# USB.net
KiCad netlist of a schematic drawn in EasyEDA Pro
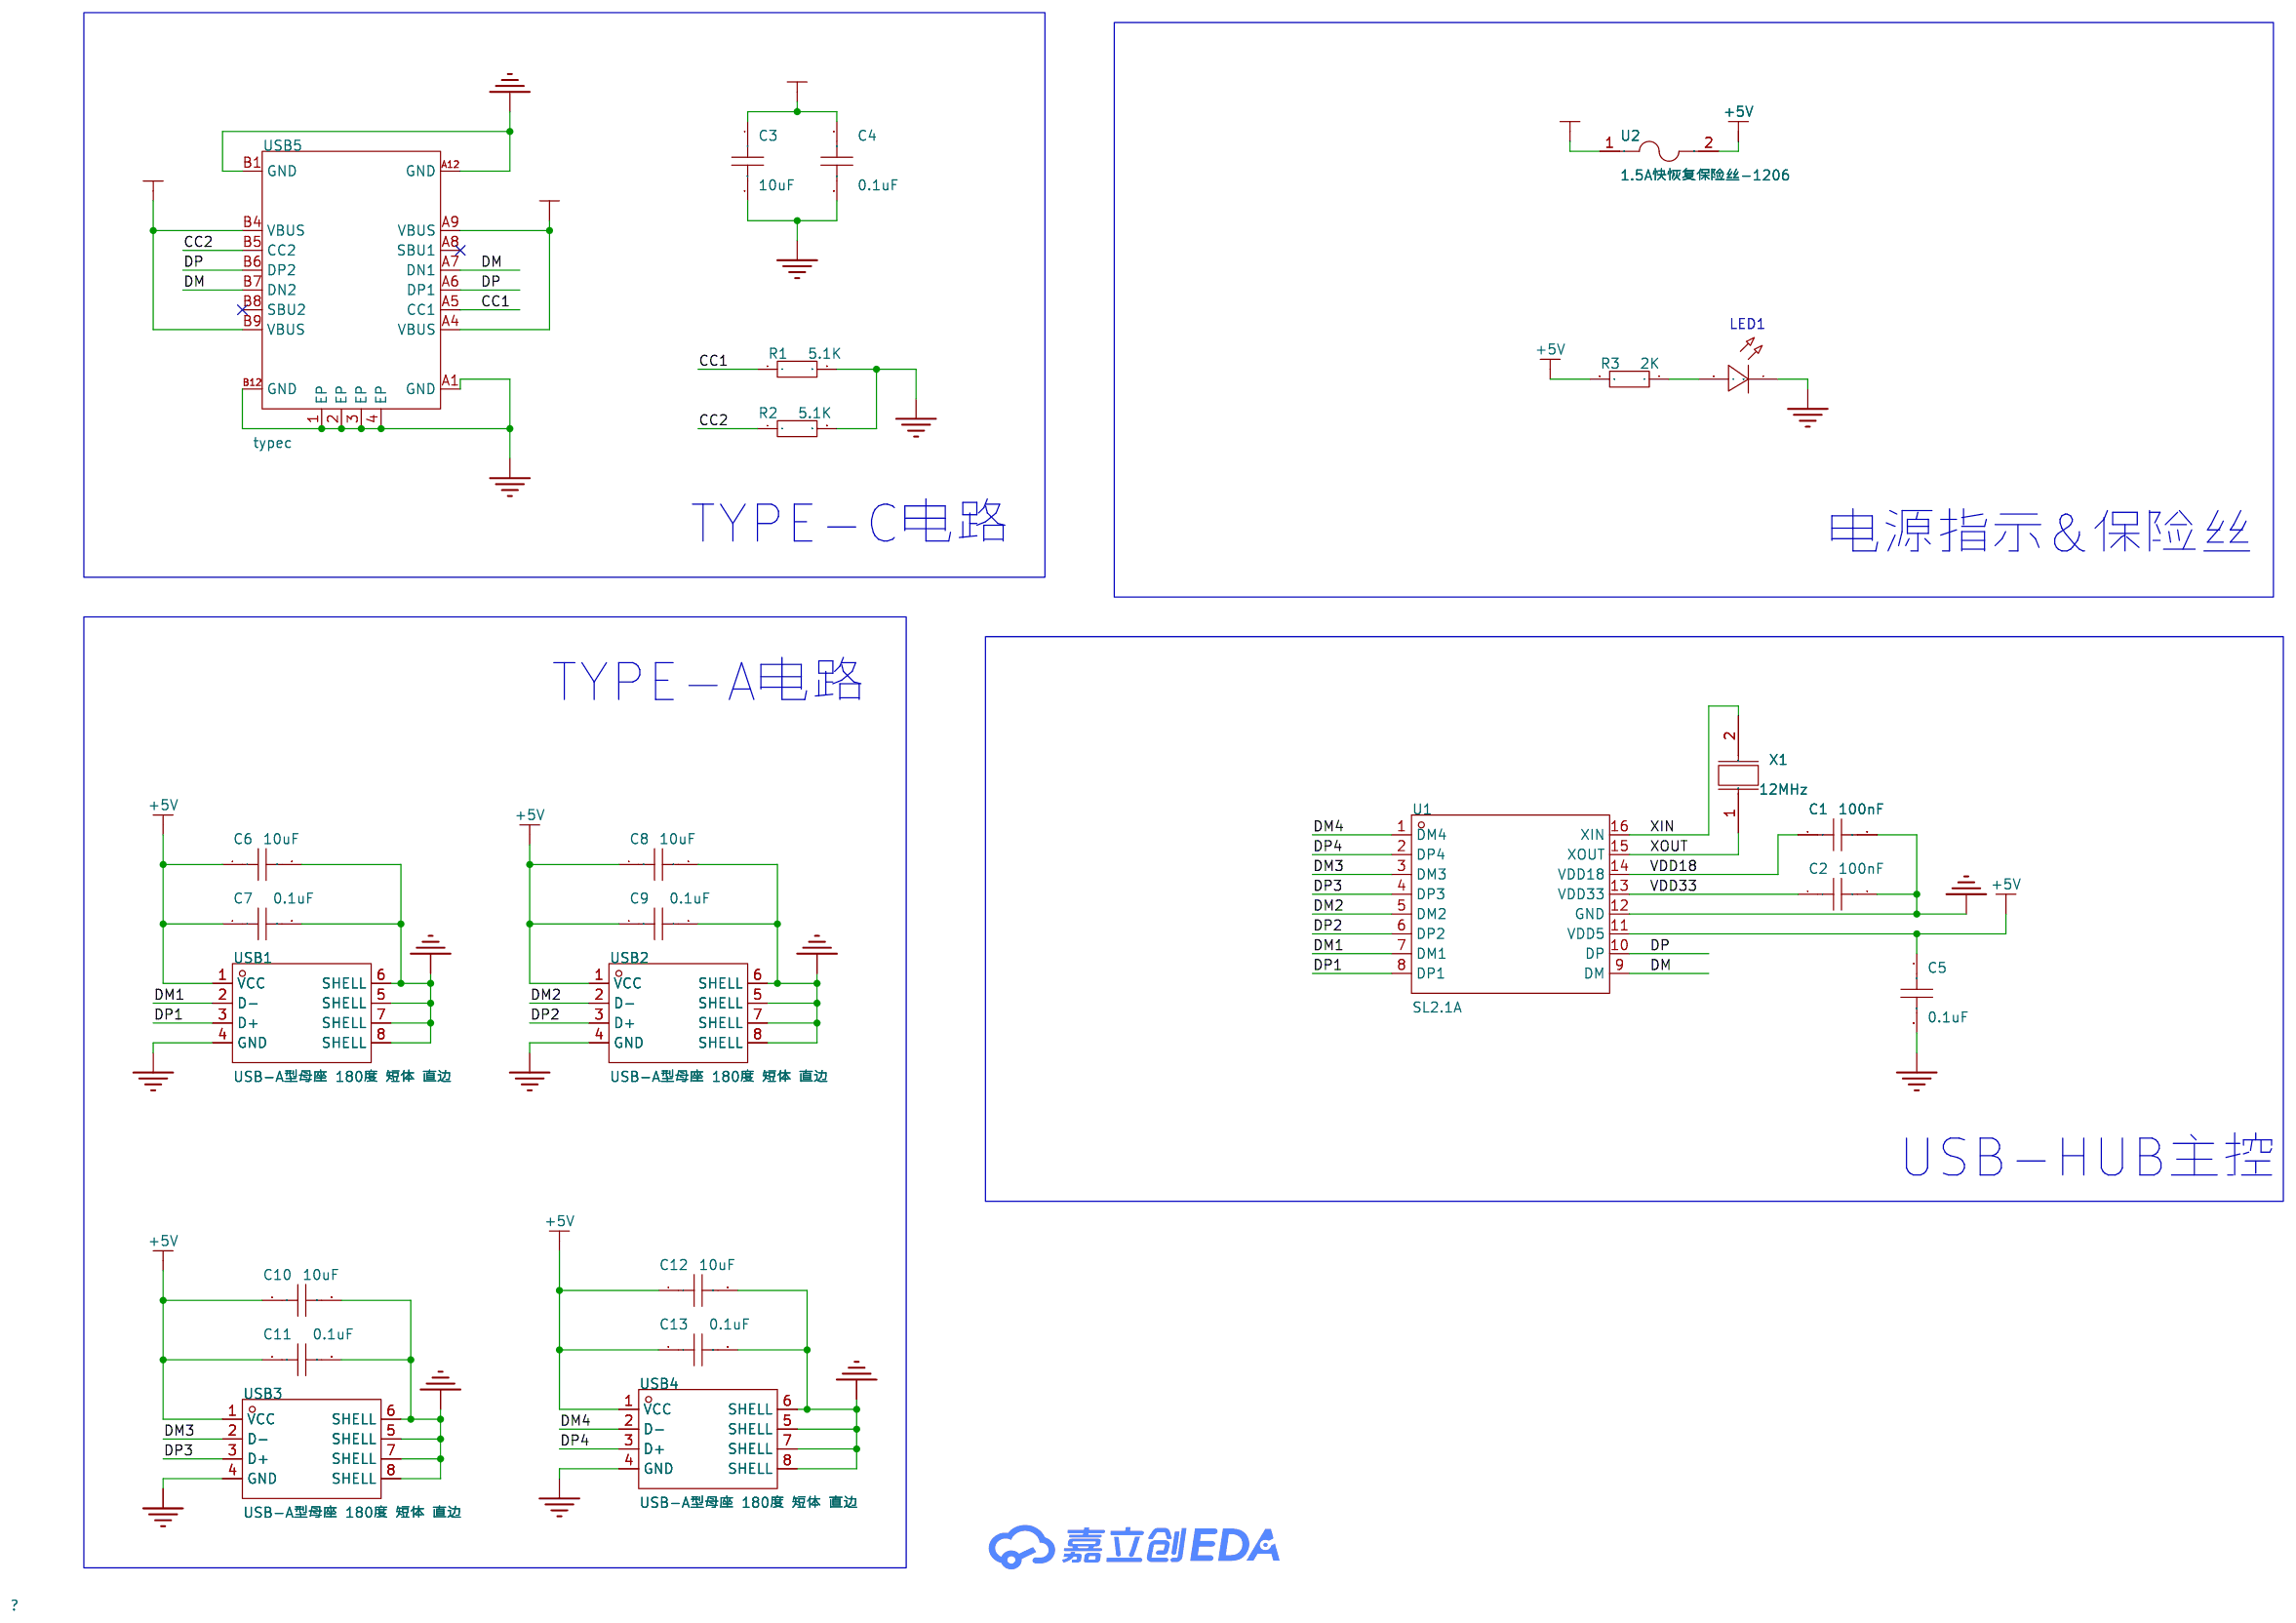
[diagram p0: schematic sheet]

(export (version "E")
  (design (tool "Eeschema 10.0.6"))
  (components
    (comp (ref "C1")
      (value "100nF")
      (footprint "easyedapro:C0805")
      (libsource (lib "easyedapro") (part "CapAcitance"))
    )
    (comp (ref "C2")
      (value "100nF")
      (footprint "easyedapro:C0805")
      (libsource (lib "easyedapro") (part "CapAcitance"))
    )
    (comp (ref "C3")
      (value "10uF")
      (footprint "easyedapro:C0805")
      (libsource (lib "easyedapro") (part "CapAcitance"))
    )
    (comp (ref "C4")
      (value "0.1uF")
      (footprint "easyedapro:C0805")
      (libsource (lib "easyedapro") (part "CapAcitance"))
    )
    (comp (ref "C5")
      (value "0.1uF")
      (footprint "easyedapro:C0805")
      (libsource (lib "easyedapro") (part "CapAcitance"))
    )
    (comp (ref "C6")
      (value "10uF")
      (footprint "easyedapro:C0805")
      (libsource (lib "easyedapro") (part "CapAcitance"))
    )
    (comp (ref "C7")
      (value "0.1uF")
      (footprint "easyedapro:C0805")
      (libsource (lib "easyedapro") (part "CapAcitance"))
    )
    (comp (ref "C8")
      (value "10uF")
      (footprint "easyedapro:C0805")
      (libsource (lib "easyedapro") (part "CapAcitance"))
    )
    (comp (ref "C9")
      (value "0.1uF")
      (footprint "easyedapro:C0805")
      (libsource (lib "easyedapro") (part "CapAcitance"))
    )
    (comp (ref "C10")
      (value "10uF")
      (footprint "easyedapro:C0805")
      (libsource (lib "easyedapro") (part "CapAcitance"))
    )
    (comp (ref "C11")
      (value "0.1uF")
      (footprint "easyedapro:C0805")
      (libsource (lib "easyedapro") (part "CapAcitance"))
    )
    (comp (ref "C12")
      (value "10uF")
      (footprint "easyedapro:C0805")
      (libsource (lib "easyedapro") (part "CapAcitance"))
    )
    (comp (ref "C13")
      (value "0.1uF")
      (footprint "easyedapro:C0805")
      (libsource (lib "easyedapro") (part "CapAcitance"))
    )
    (comp (ref "LED1")
      (value "~")
      (footprint "easyedapro:LED_0805")
      (libsource (lib "easyedapro") (part "LED_G"))
    )
    (comp (ref "R1") (value "5.1K") (footprint "easyedapro:R0603") (libsource (lib "easyedapro") (part "电阻")))
    (comp (ref "R2") (value "5.1K") (footprint "easyedapro:R0603") (libsource (lib "easyedapro") (part "电阻")))
    (comp (ref "R3") (value "2K") (footprint "easyedapro:R0603") (libsource (lib "easyedapro") (part "电阻")))
    (comp (ref "U1")
      (value "SL2.1A")
      (footprint "easyedapro:SOP-16_L10.0-W3.9-P1.27-LS6.0-BL")
      (description "SL2.1A是一颗高集成度,高性能,低功耗的USB2.0集线器主控芯片，支持USB2.0高速(480MHz),全速(12MHz)和低速模式(1.5MHz)，内置12MHz晶体振荡器。")
      (fields (field (name "Manufacturer") "CoreChips(和芯润德)"))
      (libsource (lib "easyedapro") (part "SL2.1A"))
    )
    (comp (ref "U2")
      (value "1.5A快恢复保险丝-1206")
      (footprint "easyedapro:F1206")
      (libsource (lib "easyedapro") (part "1.5A快恢复保险丝-1206"))
    )
    (comp (ref "USB1")
      (value "USB-A型母座 180度 短体 直边")
      (footprint "easyedapro:USB-A-SMD_WT_C9900004571")
      (libsource (lib "easyedapro") (part "USB-A型母座 180度 短体 直边"))
    )
    (comp (ref "USB2")
      (value "USB-A型母座 180度 短体 直边")
      (footprint "easyedapro:USB-A-SMD_WT_C9900004571")
      (libsource (lib "easyedapro") (part "USB-A型母座 180度 短体 直边"))
    )
    (comp (ref "USB3")
      (value "USB-A型母座 180度 短体 直边")
      (footprint "easyedapro:USB-A-SMD_WT_C9900004571")
      (libsource (lib "easyedapro") (part "USB-A型母座 180度 短体 直边"))
    )
    (comp (ref "USB4")
      (value "USB-A型母座 180度 短体 直边")
      (footprint "easyedapro:USB-A-SMD_WT_C9900004571")
      (libsource (lib "easyedapro") (part "USB-A型母座 180度 短体 直边"))
    )
    (comp (ref "USB5")
      (value "typec")
      (footprint "easyedapro:USB-C-SMD_KH-TYPE-C-16P")
      (libsource (lib "easyedapro") (part "TYPEC_C9900016956"))
    )
    (comp (ref "X1")
      (value "12MHz")
      (footprint "easyedapro:CRYSTAL-SMD_L5.0-W3.2-1-A")
      (libsource (lib "easyedapro") (part "12MHZ"))
    )
  )
  (nets
    (net (code "1") (name "+5V") (class "Default")
      (node (ref "C10") (pin "1") (pinfunction "1_1") (pintype "input"))
      (node (ref "C11") (pin "1") (pinfunction "1_1") (pintype "input"))
      (node (ref "C12") (pin "1") (pinfunction "1_1") (pintype "input"))
      (node (ref "C13") (pin "1") (pinfunction "1_1") (pintype "input"))
      (node (ref "C5") (pin "1") (pinfunction "1_1") (pintype "input"))
      (node (ref "C6") (pin "1") (pinfunction "1_1") (pintype "input"))
      (node (ref "C7") (pin "1") (pinfunction "1_1") (pintype "input"))
      (node (ref "C8") (pin "1") (pinfunction "1_1") (pintype "input"))
      (node (ref "C9") (pin "1") (pinfunction "1_1") (pintype "input"))
      (node (ref "R3") (pin "2") (pinfunction "2_2") (pintype "input"))
      (node (ref "U1") (pin "11") (pinfunction "VDD5_11") (pintype "unspecified"))
      (node (ref "U2") (pin "2") (pinfunction "2_2") (pintype "unspecified"))
      (node (ref "USB1") (pin "1") (pinfunction "VCC_1") (pintype "unspecified"))
      (node (ref "USB2") (pin "1") (pinfunction "VCC_1") (pintype "unspecified"))
      (node (ref "USB3") (pin "1") (pinfunction "VCC_1") (pintype "unspecified"))
      (node (ref "USB4") (pin "1") (pinfunction "VCC_1") (pintype "unspecified"))
    )
    (net (code "2") (name "/CC1") (class "Default")
      (node (ref "R1") (pin "1") (pinfunction "1_1") (pintype "input"))
      (node (ref "USB5") (pin "A5") (pinfunction "CC1_A5") (pintype "unspecified"))
    )
    (net (code "3") (name "/CC2") (class "Default")
      (node (ref "R2") (pin "1") (pinfunction "1_1") (pintype "input"))
      (node (ref "USB5") (pin "B5") (pinfunction "CC2_B5") (pintype "unspecified"))
    )
    (net (code "4") (name "/DM") (class "Default")
      (node (ref "U1") (pin "9") (pinfunction "DM_9") (pintype "unspecified"))
      (node (ref "USB5") (pin "A7") (pinfunction "DN1_A7") (pintype "unspecified"))
      (node (ref "USB5") (pin "B7") (pinfunction "DN2_B7") (pintype "unspecified"))
    )
    (net (code "5") (name "/DM1") (class "Default")
      (node (ref "U1") (pin "7") (pinfunction "DM1_7") (pintype "unspecified"))
      (node (ref "USB1") (pin "2") (pinfunction "D-_2") (pintype "unspecified"))
    )
    (net (code "6") (name "/DM2") (class "Default")
      (node (ref "U1") (pin "5") (pinfunction "DM2_5") (pintype "unspecified"))
      (node (ref "USB2") (pin "2") (pinfunction "D-_2") (pintype "unspecified"))
    )
    (net (code "7") (name "/DM3") (class "Default")
      (node (ref "U1") (pin "3") (pinfunction "DM3_3") (pintype "unspecified"))
      (node (ref "USB3") (pin "2") (pinfunction "D-_2") (pintype "unspecified"))
    )
    (net (code "8") (name "/DM4") (class "Default")
      (node (ref "U1") (pin "1") (pinfunction "DM4_1") (pintype "unspecified"))
      (node (ref "USB4") (pin "2") (pinfunction "D-_2") (pintype "unspecified"))
    )
    (net (code "9") (name "/DP") (class "Default")
      (node (ref "U1") (pin "10") (pinfunction "DP_10") (pintype "unspecified"))
      (node (ref "USB5") (pin "A6") (pinfunction "DP1_A6") (pintype "unspecified"))
      (node (ref "USB5") (pin "B6") (pinfunction "DP2_B6") (pintype "unspecified"))
    )
    (net (code "10") (name "/DP1") (class "Default")
      (node (ref "U1") (pin "8") (pinfunction "DP1_8") (pintype "unspecified"))
      (node (ref "USB1") (pin "3") (pinfunction "D+_3") (pintype "unspecified"))
    )
    (net (code "11") (name "/DP2") (class "Default")
      (node (ref "U1") (pin "6") (pinfunction "DP2_6") (pintype "unspecified"))
      (node (ref "USB2") (pin "3") (pinfunction "D+_3") (pintype "unspecified"))
    )
    (net (code "12") (name "/DP3") (class "Default")
      (node (ref "U1") (pin "4") (pinfunction "DP3_4") (pintype "unspecified"))
      (node (ref "USB3") (pin "3") (pinfunction "D+_3") (pintype "unspecified"))
    )
    (net (code "13") (name "/DP4") (class "Default")
      (node (ref "U1") (pin "2") (pinfunction "DP4_2") (pintype "unspecified"))
      (node (ref "USB4") (pin "3") (pinfunction "D+_3") (pintype "unspecified"))
    )
    (net (code "14") (name "/VDD18") (class "Default")
      (node (ref "C1") (pin "1") (pinfunction "1_1") (pintype "input"))
      (node (ref "U1") (pin "14") (pinfunction "VDD18_14") (pintype "unspecified"))
    )
    (net (code "15") (name "/VDD33") (class "Default")
      (node (ref "C2") (pin "1") (pinfunction "1_1") (pintype "input"))
      (node (ref "U1") (pin "13") (pinfunction "VDD33_13") (pintype "unspecified"))
    )
    (net (code "16") (name "/XIN") (class "Default")
      (node (ref "U1") (pin "16") (pinfunction "XIN_16") (pintype "unspecified"))
      (node (ref "X1") (pin "2") (pinfunction "2_2") (pintype "unspecified"))
    )
    (net (code "17") (name "/XOUT") (class "Default")
      (node (ref "U1") (pin "15") (pinfunction "XOUT_15") (pintype "unspecified"))
      (node (ref "X1") (pin "1") (pinfunction "1_1") (pintype "unspecified"))
    )
    (net (code "18") (name "GND") (class "Default")
      (node (ref "C1") (pin "2") (pinfunction "2_2") (pintype "input"))
      (node (ref "C10") (pin "2") (pinfunction "2_2") (pintype "input"))
      (node (ref "C11") (pin "2") (pinfunction "2_2") (pintype "input"))
      (node (ref "C12") (pin "2") (pinfunction "2_2") (pintype "input"))
      (node (ref "C13") (pin "2") (pinfunction "2_2") (pintype "input"))
      (node (ref "C2") (pin "2") (pinfunction "2_2") (pintype "input"))
      (node (ref "C3") (pin "2") (pinfunction "2_2") (pintype "input"))
      (node (ref "C4") (pin "2") (pinfunction "2_2") (pintype "input"))
      (node (ref "C5") (pin "2") (pinfunction "2_2") (pintype "input"))
      (node (ref "C6") (pin "2") (pinfunction "2_2") (pintype "input"))
      (node (ref "C7") (pin "2") (pinfunction "2_2") (pintype "input"))
      (node (ref "C8") (pin "2") (pinfunction "2_2") (pintype "input"))
      (node (ref "C9") (pin "2") (pinfunction "2_2") (pintype "input"))
      (node (ref "LED1") (pin "1") (pinfunction "C_1") (pintype "input"))
      (node (ref "R1") (pin "2") (pinfunction "2_2") (pintype "input"))
      (node (ref "R2") (pin "2") (pinfunction "2_2") (pintype "input"))
      (node (ref "U1") (pin "12") (pinfunction "GND_12") (pintype "unspecified"))
      (node (ref "USB1") (pin "4") (pinfunction "GND_4") (pintype "unspecified"))
      (node (ref "USB1") (pin "5") (pinfunction "SHELL_5") (pintype "unspecified"))
      (node (ref "USB1") (pin "6") (pinfunction "SHELL_6") (pintype "unspecified"))
      (node (ref "USB1") (pin "7") (pinfunction "SHELL_7") (pintype "unspecified"))
      (node (ref "USB1") (pin "8") (pinfunction "SHELL_8") (pintype "unspecified"))
      (node (ref "USB2") (pin "4") (pinfunction "GND_4") (pintype "unspecified"))
      (node (ref "USB2") (pin "5") (pinfunction "SHELL_5") (pintype "unspecified"))
      (node (ref "USB2") (pin "6") (pinfunction "SHELL_6") (pintype "unspecified"))
      (node (ref "USB2") (pin "7") (pinfunction "SHELL_7") (pintype "unspecified"))
      (node (ref "USB2") (pin "8") (pinfunction "SHELL_8") (pintype "unspecified"))
      (node (ref "USB3") (pin "4") (pinfunction "GND_4") (pintype "unspecified"))
      (node (ref "USB3") (pin "5") (pinfunction "SHELL_5") (pintype "unspecified"))
      (node (ref "USB3") (pin "6") (pinfunction "SHELL_6") (pintype "unspecified"))
      (node (ref "USB3") (pin "7") (pinfunction "SHELL_7") (pintype "unspecified"))
      (node (ref "USB3") (pin "8") (pinfunction "SHELL_8") (pintype "unspecified"))
      (node (ref "USB4") (pin "4") (pinfunction "GND_4") (pintype "unspecified"))
      (node (ref "USB4") (pin "5") (pinfunction "SHELL_5") (pintype "unspecified"))
      (node (ref "USB4") (pin "6") (pinfunction "SHELL_6") (pintype "unspecified"))
      (node (ref "USB4") (pin "7") (pinfunction "SHELL_7") (pintype "unspecified"))
      (node (ref "USB4") (pin "8") (pinfunction "SHELL_8") (pintype "unspecified"))
      (node (ref "USB5") (pin "1") (pinfunction "EP_1") (pintype "unspecified"))
      (node (ref "USB5") (pin "2") (pinfunction "EP_2") (pintype "unspecified"))
      (node (ref "USB5") (pin "3") (pinfunction "EP_3") (pintype "unspecified"))
      (node (ref "USB5") (pin "4") (pinfunction "EP_4") (pintype "unspecified"))
      (node (ref "USB5") (pin "A1") (pinfunction "GND_A1") (pintype "unspecified"))
      (node (ref "USB5") (pin "A12") (pinfunction "GND_A12") (pintype "unspecified"))
      (node (ref "USB5") (pin "B1") (pinfunction "GND_B1") (pintype "unspecified"))
      (node (ref "USB5") (pin "B12") (pinfunction "GND_B12") (pintype "unspecified"))
    )
    (net (code "19") (name "Net-(LED1-A)") (class "Default")
      (node (ref "LED1") (pin "2") (pinfunction "A_2") (pintype "input"))
      (node (ref "R3") (pin "1") (pinfunction "1_1") (pintype "input"))
    )
    (net (code "20") (name "VCC+5V") (class "Default")
      (node (ref "C3") (pin "1") (pinfunction "1_1") (pintype "input"))
      (node (ref "C4") (pin "1") (pinfunction "1_1") (pintype "input"))
      (node (ref "U2") (pin "1") (pinfunction "1_1") (pintype "unspecified"))
      (node (ref "USB5") (pin "A4") (pinfunction "VBUS_A4") (pintype "unspecified"))
      (node (ref "USB5") (pin "A9") (pinfunction "VBUS_A9") (pintype "unspecified"))
      (node (ref "USB5") (pin "B4") (pinfunction "VBUS_B4") (pintype "unspecified"))
      (node (ref "USB5") (pin "B9") (pinfunction "VBUS_B9") (pintype "unspecified"))
    )
    (net (code "21") (name "unconnected-(USB5-SBU1-PadA8)") (class "Default")
      (node (ref "USB5") (pin "A8") (pinfunction "SBU1_A8") (pintype "unspecified+no_connect"))
    )
    (net (code "22") (name "unconnected-(USB5-SBU2-PadB8)") (class "Default")
      (node (ref "USB5") (pin "B8") (pinfunction "SBU2_B8") (pintype "unspecified+no_connect"))
    )
  )
)
